# PAGE2.net
KiCad netlist of a schematic drawn in Altium Designer
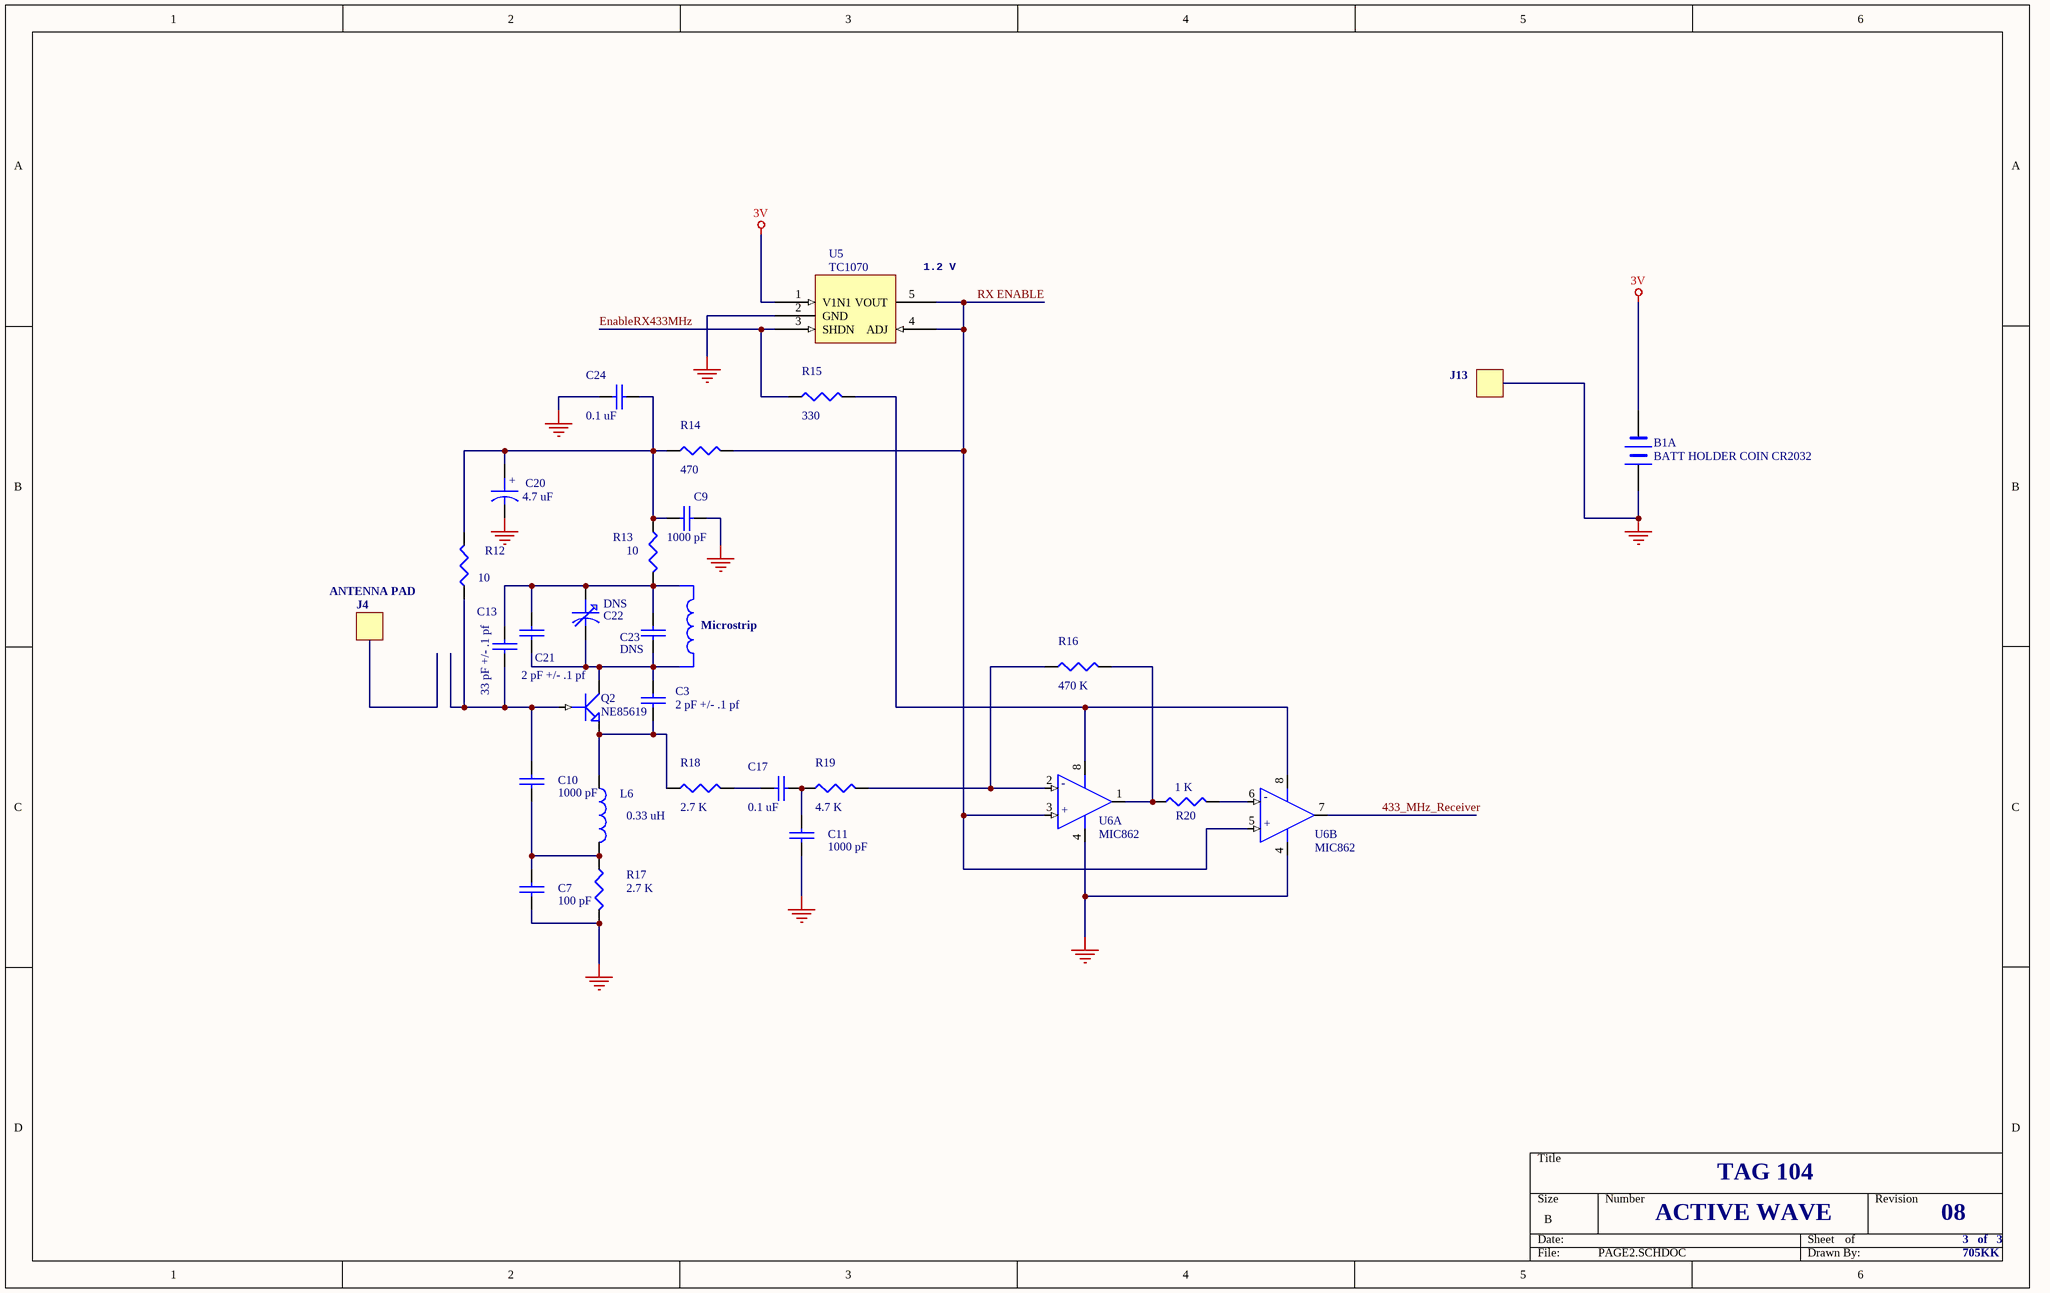
[diagram p0: PAGE2.SCHDOC]

(export (version "E")
  (design (tool "Eeschema 10.0.6"))
  (components
    (comp (ref "B1A")
      (value "BATT HOLDER COIN CR2032")
      (footprint "BATT HOLDER COIN CR2032")
      (description "Battery")
      (libsource (lib "*") (part "BATTERY"))
    )
    (comp (ref "C3")
      (value "2 pF +/- .1 pf")
      (footprint "0603")
      (description "Capacitor")
      (libsource (lib "*") (part "CAP"))
    )
    (comp (ref "C7")
      (value "100 pF")
      (footprint "0603")
      (description "Capacitor")
      (libsource (lib "*") (part "CAP"))
    )
    (comp (ref "C9")
      (value "1000 pF")
      (footprint "0603")
      (description "Capacitor")
      (libsource (lib "*") (part "CAP"))
    )
    (comp (ref "C10")
      (value "1000 pF")
      (footprint "0603")
      (description "Capacitor")
      (libsource (lib "*") (part "CAP"))
    )
    (comp (ref "C11")
      (value "1000 pF")
      (footprint "0603")
      (description "Capacitor")
      (libsource (lib "*") (part "CAP"))
    )
    (comp (ref "C13")
      (value "33 pF +/- .1 pf")
      (footprint "0603")
      (description "Capacitor")
      (libsource (lib "*") (part "CAP"))
    )
    (comp (ref "C17")
      (value "0.1 uF")
      (footprint "0603")
      (description "Capacitor")
      (libsource (lib "*") (part "CAP"))
    )
    (comp (ref "C20")
      (value "4.7 uF")
      (footprint "CAP A CASE")
      (libsource (lib "*") (part "CAPACITOR POL/SM"))
    )
    (comp (ref "C21")
      (value "2 pF +/- .1 pf")
      (footprint "0603")
      (description "Capacitor")
      (libsource (lib "*") (part "CAP"))
    )
    (comp (ref "C22") (value "DNS") (footprint "0603") (libsource (lib "*") (part "CAPACITOR VAR")))
    (comp (ref "C23")
      (value "DNS")
      (footprint "0603")
      (description "Capacitor")
      (libsource (lib "*") (part "CAP"))
    )
    (comp (ref "C24")
      (value "0.1 uF")
      (footprint "0603")
      (description "Capacitor")
      (libsource (lib "*") (part "CAP"))
    )
    (comp (ref "L6") (value "0.33 uH") (footprint "0603") (libsource (lib "*") (part "INDUCTOR")))
    (comp (ref "Q2")
      (value "NE85619")
      (footprint "3 PIN ULTRA SUPER MINI MOLD")
      (description "NPN Transistor")
      (libsource (lib "*") (part "NPN1"))
    )
    (comp (ref "R12") (value "10") (footprint "0603") (libsource (lib "*") (part "R")))
    (comp (ref "R13") (value "10") (footprint "0603") (libsource (lib "*") (part "R")))
    (comp (ref "R14") (value "470") (footprint "0603") (libsource (lib "*") (part "R")))
    (comp (ref "R15") (value "330") (footprint "0603") (libsource (lib "*") (part "R")))
    (comp (ref "R16") (value "470 K") (footprint "0603") (libsource (lib "*") (part "R")))
    (comp (ref "R17") (value "2.7 K") (footprint "0603") (libsource (lib "*") (part "RESISTOR")))
    (comp (ref "R18") (value "2.7 K") (footprint "0603") (libsource (lib "*") (part "R")))
    (comp (ref "R19") (value "4.7 K") (footprint "0603") (libsource (lib "*") (part "R")))
    (comp (ref "R20") (value "1 K") (footprint "0603") (libsource (lib "*") (part "R")))
    (comp (ref "U5") (value "TC1070") (footprint "SOT23-5A") (libsource (lib "*") (part "TC1070-2")))
    (comp (ref "U6") (value "MIC862") (footprint "SOT23-8") (libsource (lib "*") (part "MIC862")))
  )
  (nets
    (net (code "1") (name "/433_MHz_Receiver") (class "Default")
      (node (ref "U6") (pin "7") (pinfunction "OUT_7") (pintype "open_collector"))
    )
    (net (code "2") (name "/EnableRX433MHz") (class "Default")
      (node (ref "R15") (pin "1") (pinfunction "1_1") (pintype "passive"))
      (node (ref "U5") (pin "3") (pinfunction "SHDN_3") (pintype "input"))
    )
    (net (code "3") (name "/RX ENABLE") (class "Default")
      (node (ref "R14") (pin "2") (pinfunction "2_2") (pintype "passive"))
      (node (ref "U5") (pin "4") (pinfunction "ADJ_4") (pintype "input"))
      (node (ref "U5") (pin "5") (pinfunction "VOUT_5") (pintype "power_in"))
      (node (ref "U6") (pin "3") (pinfunction "+_3") (pintype "input"))
      (node (ref "U6") (pin "5") (pinfunction "+_5") (pintype "input"))
    )
    (net (code "4") (name "3V") (class "Default")
      (node (ref "B1A") (pin "2") (pinfunction "-_2") (pintype "passive"))
      (node (ref "U5") (pin "1") (pinfunction "V1N1_1") (pintype "input"))
    )
    (net (code "5") (name "GND_SIGNAL") (class "Default")
      (node (ref "B1A") (pin "1") (pinfunction "+_1") (pintype "passive"))
      (node (ref "C11") (pin "2") (pinfunction "2_2") (pintype "passive"))
      (node (ref "C20") (pin "2") (pinfunction "2_2") (pintype "passive"))
      (node (ref "C24") (pin "1") (pinfunction "1_1") (pintype "passive"))
      (node (ref "C7") (pin "2") (pinfunction "2_2") (pintype "passive"))
      (node (ref "C9") (pin "2") (pinfunction "2_2") (pintype "passive"))
      (node (ref "R17") (pin "2") (pinfunction "2_2") (pintype "passive"))
      (node (ref "U5") (pin "2") (pinfunction "GND_2") (pintype "power_in"))
      (node (ref "U6") (pin "4") (pinfunction "VSS_4") (pintype "power_in"))
    )
    (net (code "6") (name "Net-(C3-Pad2)") (class "Default")
      (node (ref "C3") (pin "2") (pinfunction "2_2") (pintype "passive"))
      (node (ref "L6") (pin "1") (pinfunction "1_1") (pintype "passive"))
      (node (ref "Q2") (pin "E") (pinfunction "E_E") (pintype "passive"))
      (node (ref "R18") (pin "1") (pinfunction "1_1") (pintype "passive"))
    )
    (net (code "7") (name "Net-(C10-Pad1)") (class "Default")
      (node (ref "C10") (pin "1") (pinfunction "1_1") (pintype "passive"))
      (node (ref "C13") (pin "1") (pinfunction "1_1") (pintype "passive"))
      (node (ref "Q2") (pin "B") (pinfunction "B_B") (pintype "input"))
      (node (ref "R12") (pin "1") (pinfunction "1_1") (pintype "passive"))
    )
    (net (code "8") (name "Net-(C10-Pad2)") (class "Default")
      (node (ref "C10") (pin "2") (pinfunction "2_2") (pintype "passive"))
      (node (ref "C7") (pin "1") (pinfunction "1_1") (pintype "passive"))
      (node (ref "L6") (pin "2") (pinfunction "2_2") (pintype "passive"))
      (node (ref "R17") (pin "1") (pinfunction "1_1") (pintype "passive"))
    )
    (net (code "9") (name "Net-(C11-Pad1)") (class "Default")
      (node (ref "C11") (pin "1") (pinfunction "1_1") (pintype "passive"))
      (node (ref "C17") (pin "2") (pinfunction "2_2") (pintype "passive"))
      (node (ref "R19") (pin "1") (pinfunction "1_1") (pintype "passive"))
    )
    (net (code "10") (name "Net-(C13-Pad2)") (class "Default")
      (node (ref "C13") (pin "2") (pinfunction "2_2") (pintype "passive"))
      (node (ref "C21") (pin "1") (pinfunction "1_1") (pintype "passive"))
      (node (ref "C22") (pin "1") (pinfunction "1_1") (pintype "passive"))
      (node (ref "C23") (pin "1") (pinfunction "1_1") (pintype "passive"))
      (node (ref "R13") (pin "2") (pinfunction "2_2") (pintype "passive"))
    )
    (net (code "11") (name "Net-(C17-Pad1)") (class "Default")
      (node (ref "C17") (pin "1") (pinfunction "1_1") (pintype "passive"))
      (node (ref "R18") (pin "2") (pinfunction "2_2") (pintype "passive"))
    )
    (net (code "12") (name "Net-(C20-Pad1)") (class "Default")
      (node (ref "C20") (pin "1") (pinfunction "1_1") (pintype "passive"))
      (node (ref "C24") (pin "2") (pinfunction "2_2") (pintype "passive"))
      (node (ref "C9") (pin "1") (pinfunction "1_1") (pintype "passive"))
      (node (ref "R12") (pin "2") (pinfunction "2_2") (pintype "passive"))
      (node (ref "R13") (pin "1") (pinfunction "1_1") (pintype "passive"))
      (node (ref "R14") (pin "1") (pinfunction "1_1") (pintype "passive"))
    )
    (net (code "13") (name "Net-(C21-Pad2)") (class "Default")
      (node (ref "C21") (pin "2") (pinfunction "2_2") (pintype "passive"))
      (node (ref "C22") (pin "2") (pinfunction "2_2") (pintype "passive"))
      (node (ref "C23") (pin "2") (pinfunction "2_2") (pintype "passive"))
      (node (ref "C3") (pin "1") (pinfunction "1_1") (pintype "passive"))
      (node (ref "Q2") (pin "C") (pinfunction "C_C") (pintype "passive"))
    )
    (net (code "14") (name "Net-(U6A--)") (class "Default")
      (node (ref "R16") (pin "1") (pinfunction "1_1") (pintype "passive"))
      (node (ref "R19") (pin "2") (pinfunction "2_2") (pintype "passive"))
      (node (ref "U6") (pin "2") (pinfunction "-_2") (pintype "input"))
    )
    (net (code "15") (name "Net-(U6A-OUT)") (class "Default")
      (node (ref "R16") (pin "2") (pinfunction "2_2") (pintype "passive"))
      (node (ref "R20") (pin "1") (pinfunction "1_1") (pintype "passive"))
      (node (ref "U6") (pin "1") (pinfunction "OUT_1") (pintype "open_collector"))
    )
    (net (code "16") (name "Net-(U6A-VDD)") (class "Default")
      (node (ref "R15") (pin "2") (pinfunction "2_2") (pintype "passive"))
      (node (ref "U6") (pin "8") (pinfunction "VDD_8") (pintype "power_in"))
    )
    (net (code "17") (name "Net-(U6B--)") (class "Default")
      (node (ref "R20") (pin "2") (pinfunction "2_2") (pintype "passive"))
      (node (ref "U6") (pin "6") (pinfunction "-_6") (pintype "input"))
    )
  )
)
